# Schematic.net
KiCad netlist of a schematic drawn in EasyEDA
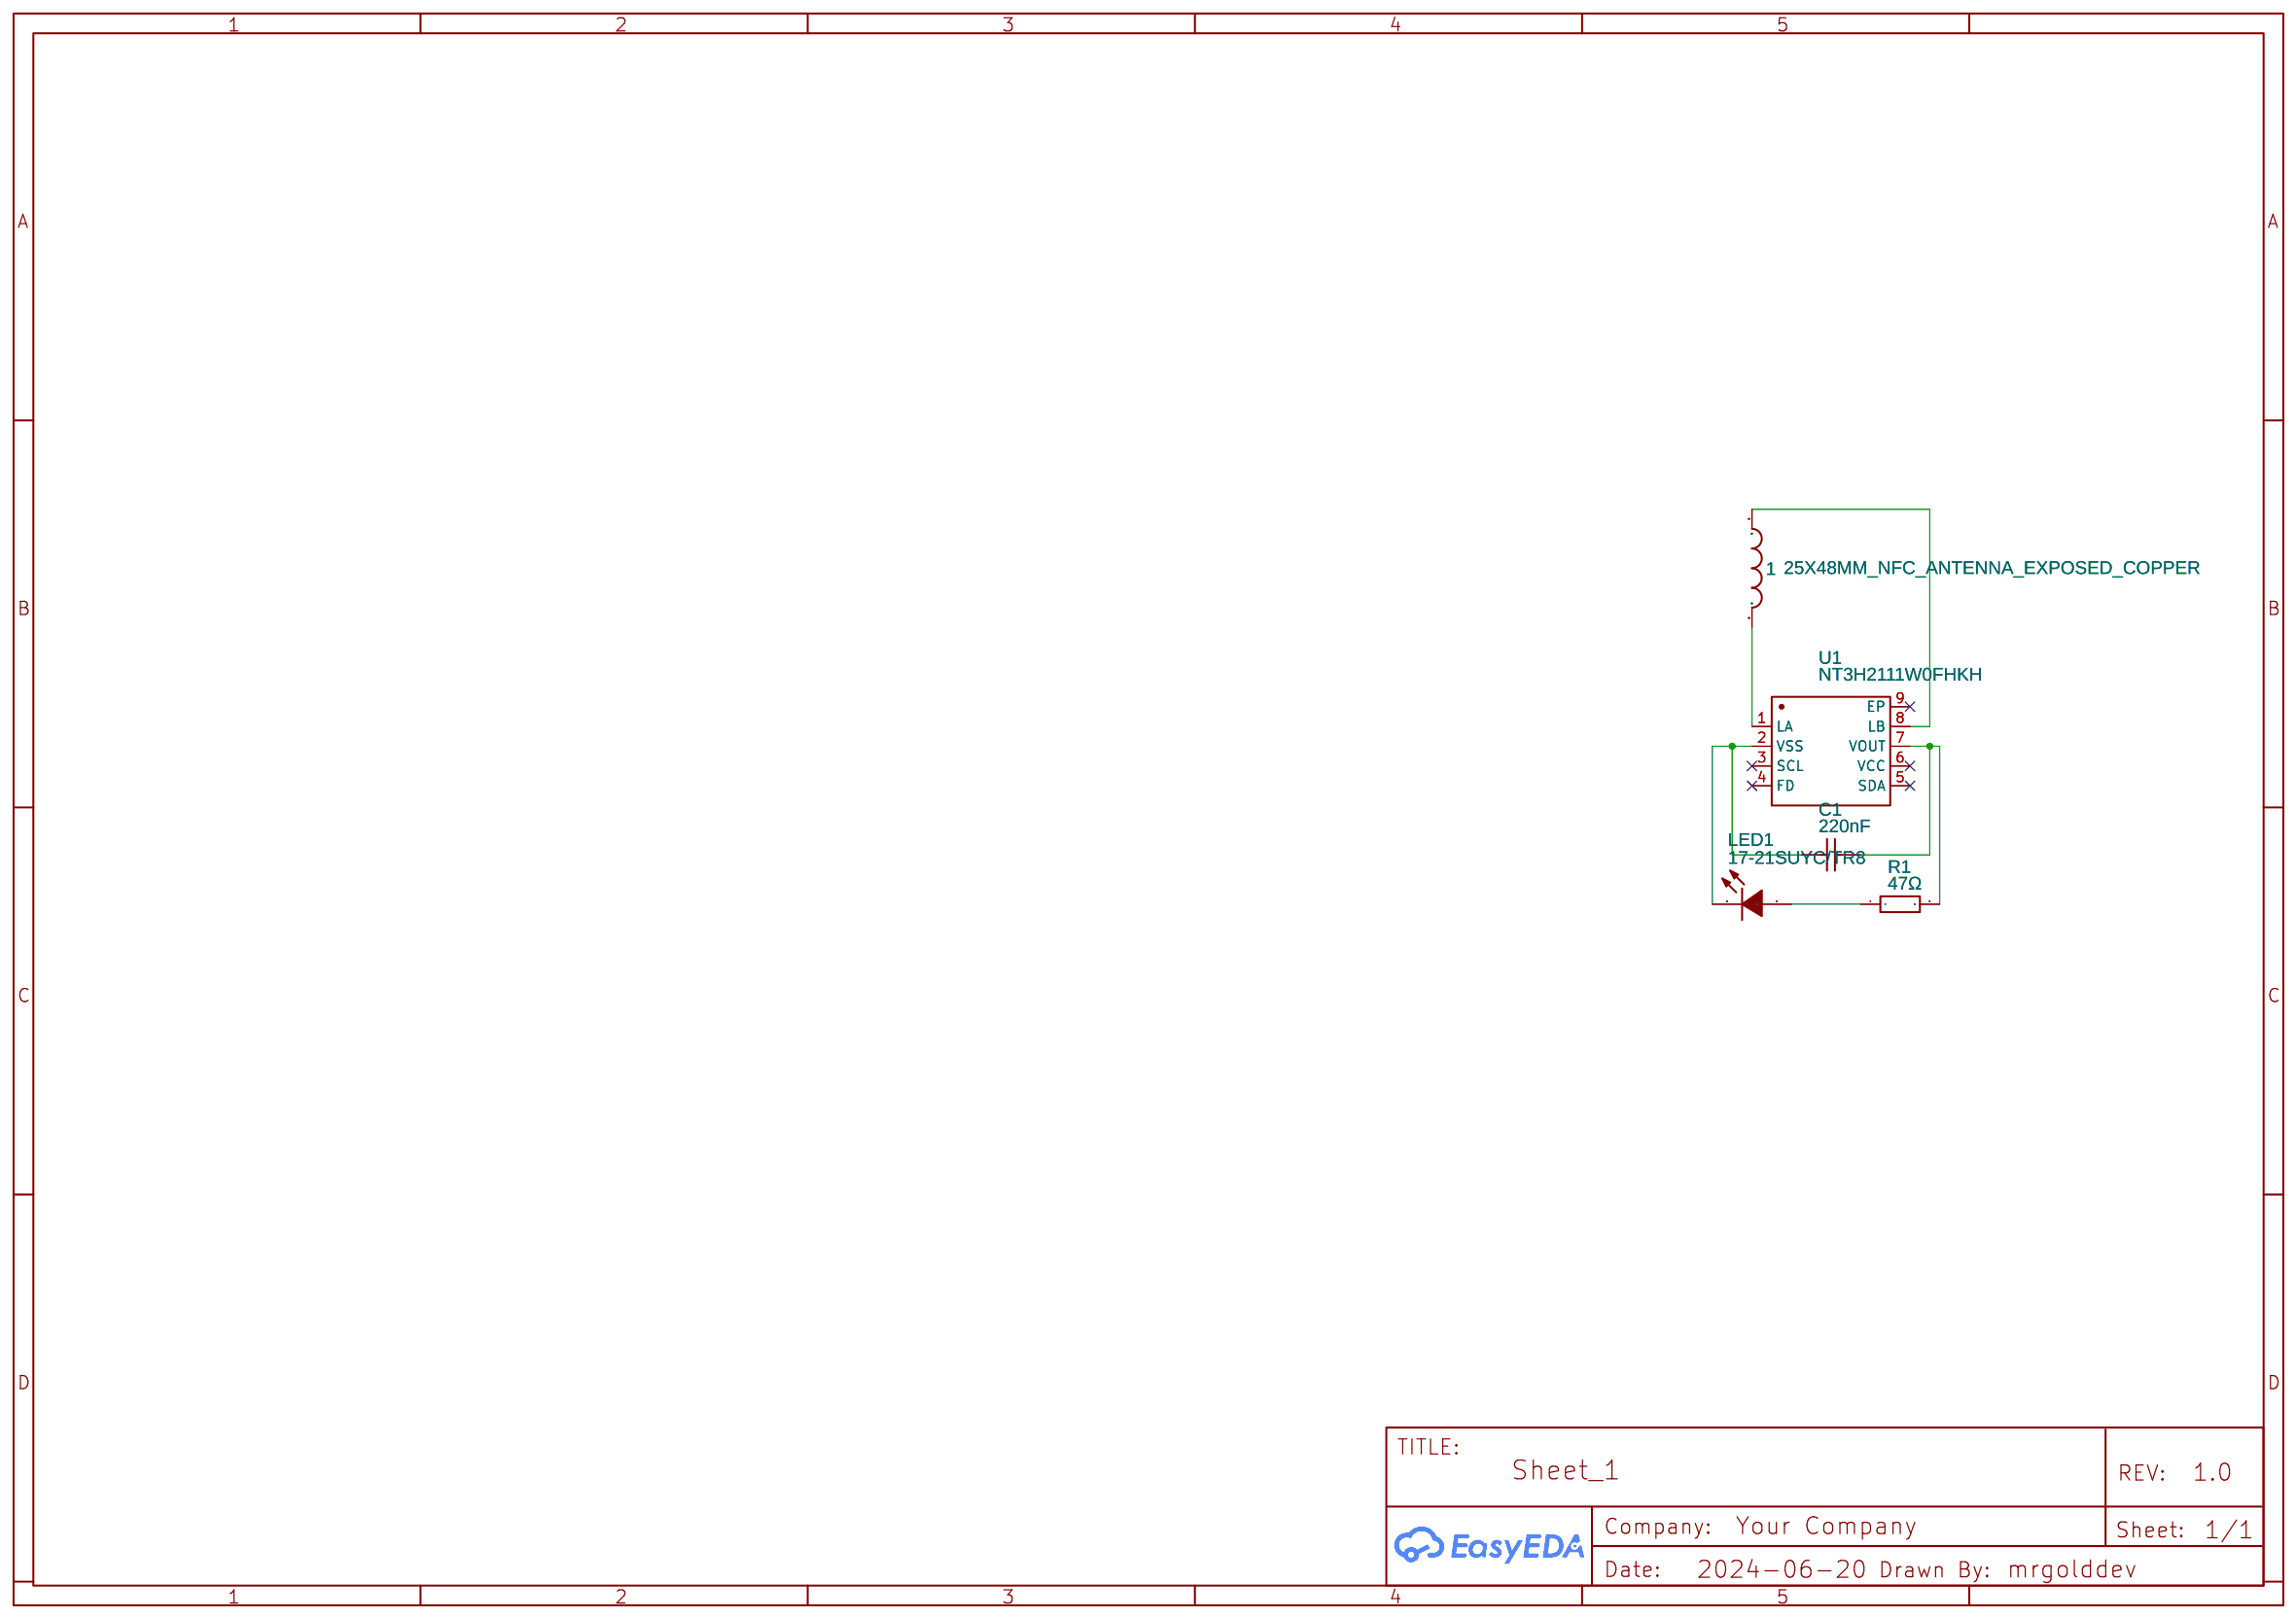
[diagram p0: schematic sheet]

(export (version "E")
  (design (tool "Eeschema 10.0.6"))
  (components
    (comp (ref "1")
      (value "25X48MM_NFC_ANTENNA_EXPOSED_COPPER")
      (libsource (lib "") (part "25X48MM_NFC_ANTENNA_EXPOSED_COPPER"))
    )
    (comp (ref "C1")
      (value "220nF")
      (fields
        (field (name "Manufacturer Part") "CL10B224KA8NNNC")
        (field (name "Manufacturer") "SAMSUNG(三星)")
      )
      (libsource (lib "") (part "CL10B224KA8NNNC"))
    )
    (comp (ref "LED1")
      (value "17-21SUYC/TR8")
      (fields (field (name "Manufacturer Part") "KT-0805黄灯") (field (name "Manufacturer") "KENTO"))
      (libsource (lib "") (part "17-21SUYC/TR8"))
    )
    (comp (ref "R1")
      (value "47Ω")
      (fields
        (field (name "Manufacturer Part") "0603WAF470JT5E")
        (field (name "Manufacturer") "UNI-ROYAL(厚声)")
      )
      (libsource (lib "") (part "0603WAF470JT5E"))
    )
    (comp (ref "U1")
      (value "NT3H2111W0FHKH")
      (fields (field (name "Manufacturer") "NXP(恩智浦)"))
      (libsource (lib "") (part "NT3H2111W0FHKH"))
    )
  )
  (nets
    (net (code "1") (name "Net-(LED1-+)") (class "Default")
      (node (ref "LED1") (pin "1") (pinfunction "+_1") (pintype "unspecified"))
      (node (ref "R1") (pin "1") (pinfunction "1_1") (pintype "input"))
    )
    (net (code "2") (name "Net-(LED1--)") (class "Default")
      (node (ref "C1") (pin "1") (pinfunction "1_1") (pintype "input"))
      (node (ref "LED1") (pin "2") (pinfunction "-_2") (pintype "unspecified"))
      (node (ref "U1") (pin "2") (pinfunction "VSS_2") (pintype "unspecified"))
    )
    (net (code "3") (name "Net-(U1-LA)") (class "Default")
      (node (ref "1") (pin "P$2") (pinfunction "P$2_P$2") (pintype "bidirectional"))
      (node (ref "U1") (pin "1") (pinfunction "LA_1") (pintype "unspecified"))
    )
    (net (code "4") (name "Net-(U1-LB)") (class "Default")
      (node (ref "1") (pin "P$1") (pinfunction "P$1_P$1") (pintype "bidirectional"))
      (node (ref "U1") (pin "8") (pinfunction "LB_8") (pintype "unspecified"))
    )
    (net (code "5") (name "Net-(U1-VOUT)") (class "Default")
      (node (ref "C1") (pin "2") (pinfunction "2_2") (pintype "input"))
      (node (ref "R1") (pin "2") (pinfunction "2_2") (pintype "input"))
      (node (ref "U1") (pin "7") (pinfunction "VOUT_7") (pintype "unspecified"))
    )
    (net (code "6") (name "unconnected-(U1-EP-Pad9)") (class "Default")
      (node (ref "U1") (pin "9") (pinfunction "EP_9") (pintype "unspecified+no_connect"))
    )
    (net (code "7") (name "unconnected-(U1-FD-Pad4)") (class "Default")
      (node (ref "U1") (pin "4") (pinfunction "FD_4") (pintype "unspecified+no_connect"))
    )
    (net (code "8") (name "unconnected-(U1-SCL-Pad3)") (class "Default")
      (node (ref "U1") (pin "3") (pinfunction "SCL_3") (pintype "unspecified+no_connect"))
    )
    (net (code "9") (name "unconnected-(U1-SDA-Pad5)") (class "Default")
      (node (ref "U1") (pin "5") (pinfunction "SDA_5") (pintype "unspecified+no_connect"))
    )
    (net (code "10") (name "unconnected-(U1-VCC-Pad6)") (class "Default")
      (node (ref "U1") (pin "6") (pinfunction "VCC_6") (pintype "unspecified+no_connect"))
    )
  )
)
